# ESPW12_taga.net
KiCad netlist of a schematic drawn in EAGLE
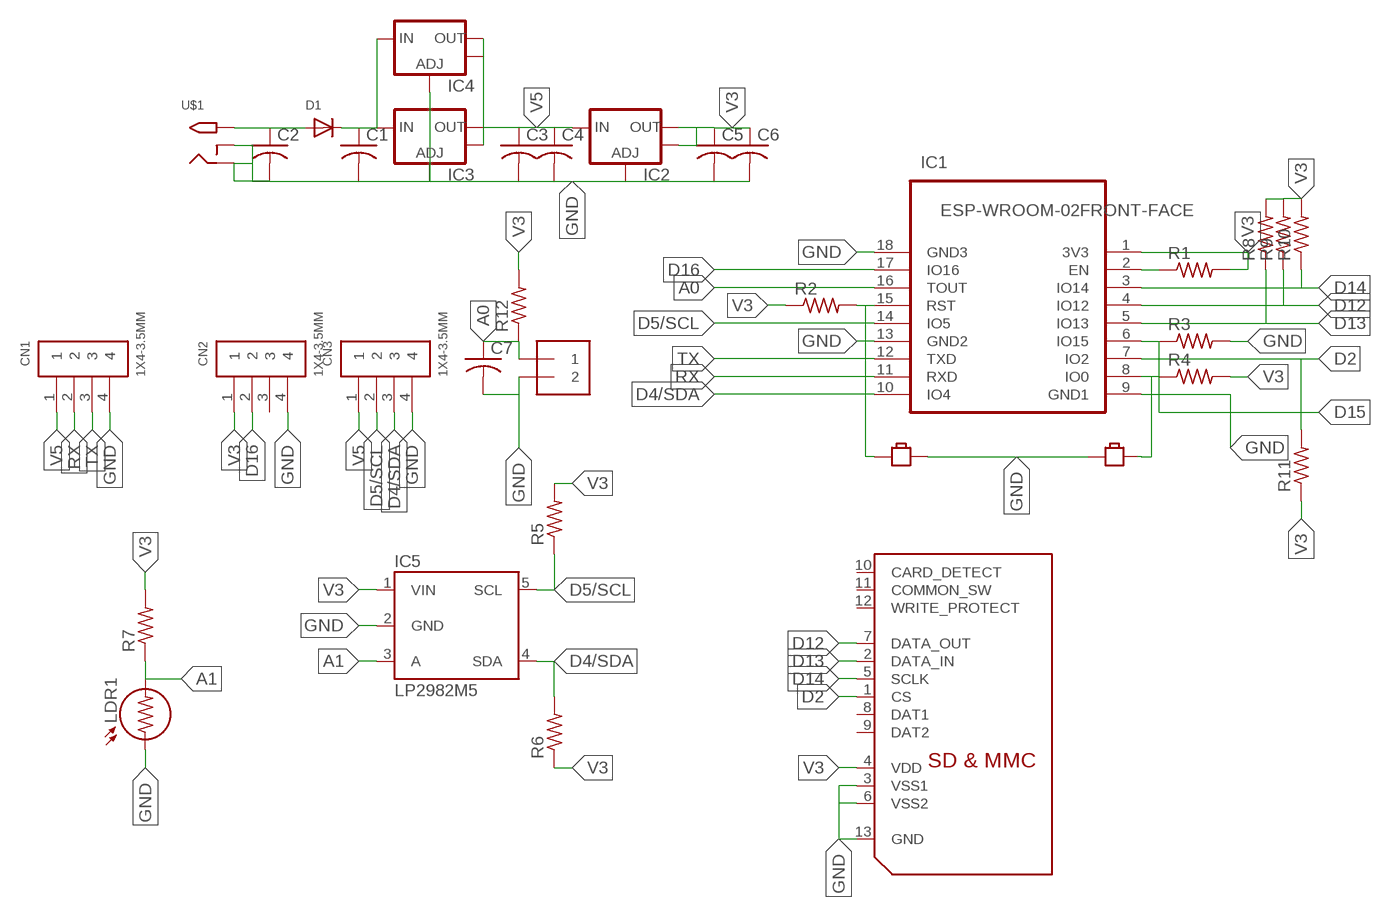
[diagram p0: schematic, sheet 1]

(export (version "E")
  (design (tool "Eeschema 10.0.6"))
  (components
    (comp (ref "B1")
      (value "BUTTON-SMD-2P")
      (footprint "eagle-import:BUTTON_2P_SMD")
      (libsource (lib "eagle-import") (part "BUTTON-SMD-2P"))
    )
    (comp (ref "B2")
      (value "BUTTON-SMD-2P")
      (footprint "eagle-import:BUTTON_2P_SMD")
      (libsource (lib "eagle-import") (part "BUTTON-SMD-2P"))
    )
    (comp (ref "C1")
      (value "C-USC0805")
      (footprint "eagle-import:C0805")
      (libsource (lib "eagle-import") (part "C-USC0805"))
    )
    (comp (ref "C2")
      (value "C-USC0805")
      (footprint "eagle-import:C0805")
      (libsource (lib "eagle-import") (part "C-USC0805"))
    )
    (comp (ref "C3")
      (value "C-USC0805")
      (footprint "eagle-import:C0805")
      (libsource (lib "eagle-import") (part "C-USC0805"))
    )
    (comp (ref "C4")
      (value "C-USC0805")
      (footprint "eagle-import:C0805")
      (libsource (lib "eagle-import") (part "C-USC0805"))
    )
    (comp (ref "C5")
      (value "C-USC0805")
      (footprint "eagle-import:C0805")
      (libsource (lib "eagle-import") (part "C-USC0805"))
    )
    (comp (ref "C6")
      (value "C-USC0805")
      (footprint "eagle-import:C0805")
      (libsource (lib "eagle-import") (part "C-USC0805"))
    )
    (comp (ref "C7")
      (value "C-USC0805")
      (footprint "eagle-import:C0805")
      (libsource (lib "eagle-import") (part "C-USC0805"))
    )
    (comp (ref "CN1")
      (value "1X4-3.5MM")
      (footprint "eagle-import:1X04-3.5MM")
      (libsource (lib "eagle-import") (part "1X4-3.5MM"))
    )
    (comp (ref "CN2")
      (value "1X4-3.5MM")
      (footprint "eagle-import:1X04-3.5MM")
      (libsource (lib "eagle-import") (part "1X4-3.5MM"))
    )
    (comp (ref "CN3")
      (value "1X4-3.5MM")
      (footprint "eagle-import:1X04-3.5MM")
      (libsource (lib "eagle-import") (part "1X4-3.5MM"))
    )
    (comp (ref "D1")
      (value "DIODESMA")
      (footprint "eagle-import:SMADIODE")
      (libsource (lib "eagle-import") (part "DIODESMA"))
    )
    (comp (ref "IC1")
      (value "ESP-WROOM-02FRONT-FACE")
      (footprint "eagle-import:FRONT-FACE")
      (libsource (lib "eagle-import") (part "ESP-WROOM-02FRONT-FACE"))
    )
    (comp (ref "IC2")
      (value "V_REG_LM1117SOT223")
      (footprint "eagle-import:SOT223")
      (libsource (lib "eagle-import") (part "V_REG_LM1117SOT223"))
    )
    (comp (ref "IC3")
      (value "V_REG_LM1117SOT223")
      (footprint "eagle-import:SOT223")
      (libsource (lib "eagle-import") (part "V_REG_LM1117SOT223"))
    )
    (comp (ref "IC4")
      (value "V_REG_LM1117SOT223")
      (footprint "eagle-import:SOT223")
      (libsource (lib "eagle-import") (part "V_REG_LM1117SOT223"))
    )
    (comp (ref "IC5")
      (value "LP2982M5")
      (footprint "eagle-import:SOT23-5")
      (libsource (lib "eagle-import") (part "LP2982M5"))
    )
    (comp (ref "J1")
      (value "1X2-3.5MM")
      (footprint "eagle-import:1X2-3.5MM")
      (libsource (lib "eagle-import") (part "1X2-3.5MM"))
    )
    (comp (ref "LDR1")
      (value "LDR5MM")
      (footprint "eagle-import:LDR338-54C")
      (libsource (lib "eagle-import") (part "LDR5MM"))
    )
    (comp (ref "R1")
      (value "R-US_R0805")
      (footprint "eagle-import:R0805")
      (libsource (lib "eagle-import") (part "R-US_R0805"))
    )
    (comp (ref "R2")
      (value "R-US_R0805")
      (footprint "eagle-import:R0805")
      (libsource (lib "eagle-import") (part "R-US_R0805"))
    )
    (comp (ref "R3")
      (value "R-US_R0805")
      (footprint "eagle-import:R0805")
      (libsource (lib "eagle-import") (part "R-US_R0805"))
    )
    (comp (ref "R4")
      (value "R-US_R0805")
      (footprint "eagle-import:R0805")
      (libsource (lib "eagle-import") (part "R-US_R0805"))
    )
    (comp (ref "R5")
      (value "R-US_R0805")
      (footprint "eagle-import:R0805")
      (libsource (lib "eagle-import") (part "R-US_R0805"))
    )
    (comp (ref "R6")
      (value "R-US_R0805")
      (footprint "eagle-import:R0805")
      (libsource (lib "eagle-import") (part "R-US_R0805"))
    )
    (comp (ref "R7")
      (value "R-US_R0805")
      (footprint "eagle-import:R0805")
      (libsource (lib "eagle-import") (part "R-US_R0805"))
    )
    (comp (ref "R8")
      (value "R-US_R0805")
      (footprint "eagle-import:R0805")
      (libsource (lib "eagle-import") (part "R-US_R0805"))
    )
    (comp (ref "R9")
      (value "R-US_R0805")
      (footprint "eagle-import:R0805")
      (libsource (lib "eagle-import") (part "R-US_R0805"))
    )
    (comp (ref "R10")
      (value "R-US_R0805")
      (footprint "eagle-import:R0805")
      (libsource (lib "eagle-import") (part "R-US_R0805"))
    )
    (comp (ref "R11")
      (value "R-US_R0805")
      (footprint "eagle-import:R0805")
      (libsource (lib "eagle-import") (part "R-US_R0805"))
    )
    (comp (ref "R12")
      (value "R-US_R0805")
      (footprint "eagle-import:R0805")
      (libsource (lib "eagle-import") (part "R-US_R0805"))
    )
    (comp (ref "U$1")
      (value "2.1MMJACKTHM")
      (footprint "eagle-import:PJ-102A")
      (libsource (lib "eagle-import") (part "2.1MMJACKTHM"))
    )
    (comp (ref "U$2")
      (value "SDMMCSCDA")
      (footprint "eagle-import:SCDA")
      (libsource (lib "eagle-import") (part "SDMMCSCDA"))
    )
  )
  (nets
    (net (code "1") (name "A0") (class "Default")
      (node (ref "C7") (pin "1") (pinfunction "1_1") (pintype "passive"))
      (node (ref "IC1") (pin "16") (pinfunction "TOUT_16") (pintype "bidirectional"))
      (node (ref "J1") (pin "1") (pinfunction "1_1") (pintype "passive"))
      (node (ref "R12") (pin "1") (pinfunction "1_1") (pintype "passive"))
    )
    (net (code "2") (name "A1") (class "Default")
      (node (ref "IC5") (pin "3") (pinfunction "A_3") (pintype "passive"))
      (node (ref "LDR1") (pin "2") (pinfunction "2_2") (pintype "passive"))
      (node (ref "R7") (pin "1") (pinfunction "1_1") (pintype "passive"))
    )
    (net (code "3") (name "D2") (class "Default")
      (node (ref "IC1") (pin "7") (pinfunction "IO2_7") (pintype "bidirectional"))
      (node (ref "R11") (pin "2") (pinfunction "2_2") (pintype "passive"))
      (node (ref "U$2") (pin "1") (pinfunction "CS_1") (pintype "input"))
    )
    (net (code "4") (name "D4{slash}SDA") (class "Default")
      (node (ref "CN3") (pin "3") (pinfunction "3_3") (pintype "bidirectional"))
      (node (ref "IC1") (pin "10") (pinfunction "IO4_10") (pintype "bidirectional"))
      (node (ref "IC5") (pin "4") (pinfunction "SDA_4") (pintype "power_in"))
      (node (ref "R6") (pin "2") (pinfunction "2_2") (pintype "passive"))
    )
    (net (code "5") (name "D5{slash}SCL") (class "Default")
      (node (ref "CN3") (pin "2") (pinfunction "2_2") (pintype "bidirectional"))
      (node (ref "IC1") (pin "14") (pinfunction "IO5_14") (pintype "open_collector"))
      (node (ref "IC5") (pin "5") (pinfunction "SCL_5") (pintype "output"))
      (node (ref "R5") (pin "1") (pinfunction "1_1") (pintype "passive"))
    )
    (net (code "6") (name "D12") (class "Default")
      (node (ref "IC1") (pin "4") (pinfunction "IO12_4") (pintype "bidirectional"))
      (node (ref "R9") (pin "1") (pinfunction "1_1") (pintype "passive"))
      (node (ref "U$2") (pin "7") (pinfunction "DATA_OUT_7") (pintype "output"))
    )
    (net (code "7") (name "D13") (class "Default")
      (node (ref "IC1") (pin "5") (pinfunction "IO13_5") (pintype "bidirectional"))
      (node (ref "R8") (pin "1") (pinfunction "1_1") (pintype "passive"))
      (node (ref "U$2") (pin "2") (pinfunction "DATA_IN_2") (pintype "input"))
    )
    (net (code "8") (name "D14") (class "Default")
      (node (ref "IC1") (pin "3") (pinfunction "IO14_3") (pintype "bidirectional"))
      (node (ref "R10") (pin "1") (pinfunction "1_1") (pintype "passive"))
      (node (ref "U$2") (pin "5") (pinfunction "SCLK_5") (pintype "input"))
    )
    (net (code "9") (name "D15") (class "Default")
      (node (ref "IC1") (pin "6") (pinfunction "IO15_6") (pintype "bidirectional"))
      (node (ref "R3") (pin "1") (pinfunction "1_1") (pintype "passive"))
    )
    (net (code "10") (name "D16") (class "Default")
      (node (ref "CN2") (pin "2") (pinfunction "2_2") (pintype "bidirectional"))
      (node (ref "IC1") (pin "17") (pinfunction "IO16_17") (pintype "bidirectional"))
    )
    (net (code "11") (name "GND") (class "Default")
      (node (ref "B1") (pin "P$2") (pinfunction "P$2_P$2") (pintype "bidirectional"))
      (node (ref "B2") (pin "1") (pinfunction "P$1_1") (pintype "bidirectional"))
      (node (ref "C1") (pin "2") (pinfunction "2_2") (pintype "passive"))
      (node (ref "C2") (pin "2") (pinfunction "2_2") (pintype "passive"))
      (node (ref "C3") (pin "2") (pinfunction "2_2") (pintype "passive"))
      (node (ref "C4") (pin "2") (pinfunction "2_2") (pintype "passive"))
      (node (ref "C5") (pin "2") (pinfunction "2_2") (pintype "passive"))
      (node (ref "C6") (pin "2") (pinfunction "2_2") (pintype "passive"))
      (node (ref "C7") (pin "2") (pinfunction "2_2") (pintype "passive"))
      (node (ref "CN1") (pin "4") (pinfunction "4_4") (pintype "bidirectional"))
      (node (ref "CN2") (pin "4") (pinfunction "4_4") (pintype "bidirectional"))
      (node (ref "CN3") (pin "4") (pinfunction "4_4") (pintype "bidirectional"))
      (node (ref "IC1") (pin "13") (pinfunction "GND2_13") (pintype "power_in"))
      (node (ref "IC1") (pin "18") (pinfunction "GND3_18") (pintype "power_in"))
      (node (ref "IC1") (pin "9") (pinfunction "GND1_9") (pintype "power_in"))
      (node (ref "IC2") (pin "1") (pinfunction "ADJ_1") (pintype "input"))
      (node (ref "IC3") (pin "1") (pinfunction "ADJ_1") (pintype "input"))
      (node (ref "IC4") (pin "1") (pinfunction "ADJ_1") (pintype "input"))
      (node (ref "IC5") (pin "2") (pinfunction "GND_2") (pintype "input"))
      (node (ref "J1") (pin "2") (pinfunction "2_2") (pintype "passive"))
      (node (ref "LDR1") (pin "1") (pinfunction "1_1") (pintype "passive"))
      (node (ref "R3") (pin "2") (pinfunction "2_2") (pintype "passive"))
      (node (ref "U$1") (pin "RING") (pinfunction "RING_RING") (pintype "bidirectional"))
      (node (ref "U$1") (pin "RING_SW") (pinfunction "RING_SW_RING_SW") (pintype "bidirectional"))
      (node (ref "U$2") (pin "13") (pinfunction "GND_13") (pintype "power_in"))
      (node (ref "U$2") (pin "3") (pinfunction "VSS1_3") (pintype "power_in"))
      (node (ref "U$2") (pin "6") (pinfunction "VSS2_6") (pintype "power_in"))
    )
    (net (code "12") (name "Net-(B1-P$1)") (class "Default")
      (node (ref "B1") (pin "1") (pinfunction "P$1_1") (pintype "bidirectional"))
      (node (ref "IC1") (pin "15") (pinfunction "RST_15") (pintype "bidirectional"))
      (node (ref "R2") (pin "2") (pinfunction "2_2") (pintype "passive"))
    )
    (net (code "13") (name "Net-(C2-Pad1)") (class "Default")
      (node (ref "C2") (pin "1") (pinfunction "1_1") (pintype "passive"))
      (node (ref "D1") (pin "A") (pinfunction "A_A") (pintype "passive"))
      (node (ref "U$1") (pin "TIP") (pinfunction "TIP_TIP") (pintype "bidirectional"))
    )
    (net (code "14") (name "Net-(IC1-EN)") (class "Default")
      (node (ref "IC1") (pin "2") (pinfunction "EN_2") (pintype "bidirectional"))
      (node (ref "R1") (pin "1") (pinfunction "1_1") (pintype "passive"))
    )
    (net (code "15") (name "Net-(IC1-IO0)") (class "Default")
      (node (ref "B2") (pin "P$2") (pinfunction "P$2_P$2") (pintype "bidirectional"))
      (node (ref "IC1") (pin "8") (pinfunction "IO0_8") (pintype "bidirectional"))
      (node (ref "R4") (pin "1") (pinfunction "1_1") (pintype "passive"))
    )
    (net (code "16") (name "Net-(IC3-IN)") (class "Default")
      (node (ref "C1") (pin "1") (pinfunction "1_1") (pintype "passive"))
      (node (ref "D1") (pin "C") (pinfunction "C_C") (pintype "passive"))
      (node (ref "IC3") (pin "3") (pinfunction "IN_3") (pintype "input"))
      (node (ref "IC4") (pin "3") (pinfunction "IN_3") (pintype "input"))
    )
    (net (code "17") (name "RX") (class "Default")
      (node (ref "CN1") (pin "2") (pinfunction "2_2") (pintype "bidirectional"))
      (node (ref "IC1") (pin "11") (pinfunction "RXD_11") (pintype "bidirectional"))
    )
    (net (code "18") (name "TX") (class "Default")
      (node (ref "CN1") (pin "3") (pinfunction "3_3") (pintype "bidirectional"))
      (node (ref "IC1") (pin "12") (pinfunction "TXD_12") (pintype "bidirectional"))
    )
    (net (code "19") (name "V3") (class "Default")
      (node (ref "C5") (pin "1") (pinfunction "1_1") (pintype "passive"))
      (node (ref "C6") (pin "1") (pinfunction "1_1") (pintype "passive"))
      (node (ref "CN2") (pin "1") (pinfunction "1_1") (pintype "bidirectional"))
      (node (ref "IC1") (pin "1") (pinfunction "3V3_1") (pintype "power_in"))
      (node (ref "IC2") (pin "2") (pinfunction "OUT_2") (pintype "output"))
      (node (ref "IC2") (pin "4") (pinfunction "OUT_4") (pintype "output"))
      (node (ref "IC5") (pin "1") (pinfunction "VIN_1") (pintype "power_in"))
      (node (ref "R1") (pin "2") (pinfunction "2_2") (pintype "passive"))
      (node (ref "R10") (pin "2") (pinfunction "2_2") (pintype "passive"))
      (node (ref "R11") (pin "1") (pinfunction "1_1") (pintype "passive"))
      (node (ref "R12") (pin "2") (pinfunction "2_2") (pintype "passive"))
      (node (ref "R2") (pin "1") (pinfunction "1_1") (pintype "passive"))
      (node (ref "R4") (pin "2") (pinfunction "2_2") (pintype "passive"))
      (node (ref "R5") (pin "2") (pinfunction "2_2") (pintype "passive"))
      (node (ref "R6") (pin "1") (pinfunction "1_1") (pintype "passive"))
      (node (ref "R7") (pin "2") (pinfunction "2_2") (pintype "passive"))
      (node (ref "R8") (pin "2") (pinfunction "2_2") (pintype "passive"))
      (node (ref "R9") (pin "2") (pinfunction "2_2") (pintype "passive"))
      (node (ref "U$2") (pin "4") (pinfunction "VDD_4") (pintype "power_in"))
    )
    (net (code "20") (name "V5") (class "Default")
      (node (ref "C3") (pin "1") (pinfunction "1_1") (pintype "passive"))
      (node (ref "C4") (pin "1") (pinfunction "1_1") (pintype "passive"))
      (node (ref "CN1") (pin "1") (pinfunction "1_1") (pintype "bidirectional"))
      (node (ref "CN3") (pin "1") (pinfunction "1_1") (pintype "bidirectional"))
      (node (ref "IC2") (pin "3") (pinfunction "IN_3") (pintype "input"))
      (node (ref "IC3") (pin "2") (pinfunction "OUT_2") (pintype "output"))
      (node (ref "IC3") (pin "4") (pinfunction "OUT_4") (pintype "output"))
      (node (ref "IC4") (pin "2") (pinfunction "OUT_2") (pintype "output"))
      (node (ref "IC4") (pin "4") (pinfunction "OUT_4") (pintype "output"))
    )
    (net (code "21") (name "unconnected-(CN2-Pad3)") (class "Default")
      (node (ref "CN2") (pin "3") (pinfunction "3_3") (pintype "bidirectional"))
    )
    (net (code "22") (name "unconnected-(U$2-CARD_DETECT-Pad10)") (class "Default")
      (node (ref "U$2") (pin "10") (pinfunction "CARD_DETECT_10") (pintype "passive"))
    )
    (net (code "23") (name "unconnected-(U$2-COMMON_SW-Pad11)") (class "Default")
      (node (ref "U$2") (pin "11") (pinfunction "COMMON_SW_11") (pintype "passive"))
    )
    (net (code "24") (name "unconnected-(U$2-DAT1-Pad8)") (class "Default")
      (node (ref "U$2") (pin "8") (pinfunction "DAT1_8") (pintype "bidirectional"))
    )
    (net (code "25") (name "unconnected-(U$2-DAT2-Pad9)") (class "Default")
      (node (ref "U$2") (pin "9") (pinfunction "DAT2_9") (pintype "bidirectional"))
    )
    (net (code "26") (name "unconnected-(U$2-WRITE_PROTECT-Pad12)") (class "Default")
      (node (ref "U$2") (pin "12") (pinfunction "WRITE_PROTECT_12") (pintype "passive"))
    )
  )
)
